# Board.net
KiCad netlist of a schematic drawn in EAGLE
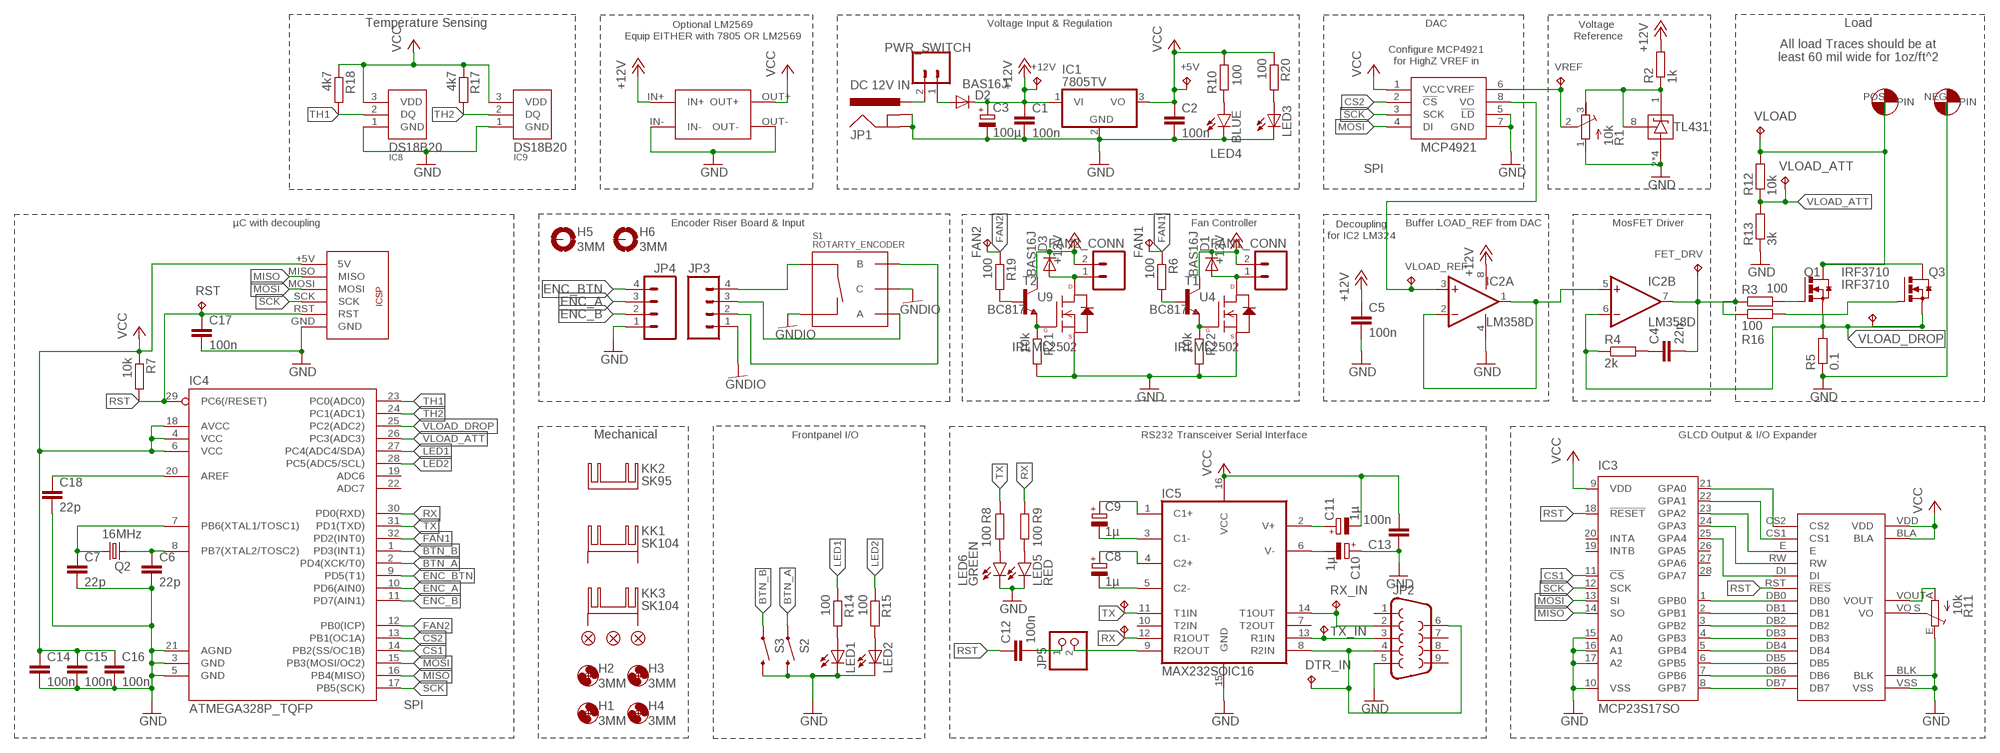
[diagram p0: schematic, sheet 1]

(export (version "E")
  (design (tool "Eeschema 10.0.6"))
  (components
    (comp (ref "+5V")
      (value "TPB1,27")
      (footprint "eagle-import:B1,27")
      (libsource (lib "eagle-import") (part "TPB1,27"))
    )
    (comp (ref "+12V")
      (value "TPB1,27")
      (footprint "eagle-import:B1,27")
      (libsource (lib "eagle-import") (part "TPB1,27"))
    )
    (comp (ref "C1")
      (value "100n")
      (footprint "eagle-import:C1206K")
      (libsource (lib "eagle-import") (part "C-EUC1206K"))
    )
    (comp (ref "C2")
      (value "100n")
      (footprint "eagle-import:C1206K")
      (libsource (lib "eagle-import") (part "C-EUC1206K"))
    )
    (comp (ref "C3")
      (value "100µ")
      (footprint "eagle-import:175TMP-0808")
      (libsource (lib "eagle-import") (part "CPOL-EU175TMP-0808"))
    )
    (comp (ref "C4")
      (value "22n")
      (footprint "eagle-import:C1206")
      (libsource (lib "eagle-import") (part "C-EUC1206"))
    )
    (comp (ref "C5")
      (value "100n")
      (footprint "eagle-import:C1206K")
      (libsource (lib "eagle-import") (part "C-EUC1206K"))
    )
    (comp (ref "C6")
      (value "22p")
      (footprint "eagle-import:C1206K")
      (libsource (lib "eagle-import") (part "C-EUC1206K"))
    )
    (comp (ref "C7")
      (value "22p")
      (footprint "eagle-import:C1206K")
      (libsource (lib "eagle-import") (part "C-EUC1206K"))
    )
    (comp (ref "C8")
      (value "1µ")
      (footprint "eagle-import:153CLV-0405")
      (libsource (lib "eagle-import") (part "CPOL-EU153CLV-0405"))
    )
    (comp (ref "C9")
      (value "1µ")
      (footprint "eagle-import:153CLV-0405")
      (libsource (lib "eagle-import") (part "CPOL-EU153CLV-0405"))
    )
    (comp (ref "C10")
      (value "1µ")
      (footprint "eagle-import:153CLV-0405")
      (libsource (lib "eagle-import") (part "CPOL-EU153CLV-0405"))
    )
    (comp (ref "C11")
      (value "1µ")
      (footprint "eagle-import:153CLV-0405")
      (libsource (lib "eagle-import") (part "CPOL-EU153CLV-0405"))
    )
    (comp (ref "C12")
      (value "100n")
      (footprint "eagle-import:C1206K")
      (libsource (lib "eagle-import") (part "C-EUC1206K"))
    )
    (comp (ref "C13")
      (value "100n")
      (footprint "eagle-import:C1206K")
      (libsource (lib "eagle-import") (part "C-EUC1206K"))
    )
    (comp (ref "C14")
      (value "100n")
      (footprint "eagle-import:C1206K")
      (libsource (lib "eagle-import") (part "C-EUC1206K"))
    )
    (comp (ref "C15")
      (value "100n")
      (footprint "eagle-import:C1206K")
      (libsource (lib "eagle-import") (part "C-EUC1206K"))
    )
    (comp (ref "C16")
      (value "100n")
      (footprint "eagle-import:C1206K")
      (libsource (lib "eagle-import") (part "C-EUC1206K"))
    )
    (comp (ref "C17")
      (value "100n")
      (footprint "eagle-import:C1206K")
      (libsource (lib "eagle-import") (part "C-EUC1206K"))
    )
    (comp (ref "C18")
      (value "22p")
      (footprint "eagle-import:C1206K")
      (libsource (lib "eagle-import") (part "C-EUC1206K"))
    )
    (comp (ref "D1")
      (value "BAS16J")
      (footprint "eagle-import:SOD323-W")
      (libsource (lib "eagle-import") (part "DIODE-SOD323-W"))
    )
    (comp (ref "D2")
      (value "BAS16J")
      (footprint "eagle-import:SOD323-W")
      (libsource (lib "eagle-import") (part "DIODE-SOD323-W"))
    )
    (comp (ref "D3")
      (value "BAS16J")
      (footprint "eagle-import:SOD323-W")
      (libsource (lib "eagle-import") (part "DIODE-SOD323-W"))
    )
    (comp (ref "DTR_IN")
      (value "TPB1,27")
      (footprint "eagle-import:B1,27")
      (libsource (lib "eagle-import") (part "TPB1,27"))
    )
    (comp (ref "FAN1")
      (value "TPB1,27")
      (footprint "eagle-import:B1,27")
      (libsource (lib "eagle-import") (part "TPB1,27"))
    )
    (comp (ref "FAN1_CONN")
      (value "M02POLAR")
      (footprint "eagle-import:MOLEX-1X2")
      (libsource (lib "eagle-import") (part "M02POLAR"))
    )
    (comp (ref "FAN2")
      (value "TPB1,27")
      (footprint "eagle-import:B1,27")
      (libsource (lib "eagle-import") (part "TPB1,27"))
    )
    (comp (ref "FAN2_CONN")
      (value "M02POLAR")
      (footprint "eagle-import:MOLEX-1X2")
      (libsource (lib "eagle-import") (part "M02POLAR"))
    )
    (comp (ref "FET_DRV")
      (value "TPB1,27")
      (footprint "eagle-import:B1,27")
      (libsource (lib "eagle-import") (part "TPB1,27"))
    )
    (comp (ref "FID1")
      (value "FIDUCIAL1X2")
      (footprint "eagle-import:FIDUCIAL-1X2")
      (libsource (lib "eagle-import") (part "FIDUCIAL1X2"))
    )
    (comp (ref "FID2")
      (value "FIDUCIAL1X2")
      (footprint "eagle-import:FIDUCIAL-1X2")
      (libsource (lib "eagle-import") (part "FIDUCIAL1X2"))
    )
    (comp (ref "FID3")
      (value "FIDUCIAL1X2")
      (footprint "eagle-import:FIDUCIAL-1X2")
      (libsource (lib "eagle-import") (part "FIDUCIAL1X2"))
    )
    (comp (ref "H1")
      (value "3MM")
      (footprint "eagle-import:3,0")
      (libsource (lib "eagle-import") (part "MOUNT-HOLE3.0"))
    )
    (comp (ref "H2")
      (value "3MM")
      (footprint "eagle-import:3,0")
      (libsource (lib "eagle-import") (part "MOUNT-HOLE3.0"))
    )
    (comp (ref "H3")
      (value "3MM")
      (footprint "eagle-import:3,0")
      (libsource (lib "eagle-import") (part "MOUNT-HOLE3.0"))
    )
    (comp (ref "H4")
      (value "3MM")
      (footprint "eagle-import:3,0")
      (libsource (lib "eagle-import") (part "MOUNT-HOLE3.0"))
    )
    (comp (ref "H5")
      (value "3MM")
      (footprint "eagle-import:3,0-PAD")
      (libsource (lib "eagle-import") (part "MOUNT-PAD-ROUND3.0"))
    )
    (comp (ref "H6")
      (value "3MM")
      (footprint "eagle-import:3,0-PAD")
      (libsource (lib "eagle-import") (part "MOUNT-PAD-ROUND3.0"))
    )
    (comp (ref "IC1")
      (value "7805TV")
      (footprint "eagle-import:TO220V")
      (libsource (lib "eagle-import") (part "78TV05"))
    )
    (comp (ref "IC2")
      (value "LM358D")
      (footprint "eagle-import:SO08")
      (libsource (lib "eagle-import") (part "LM358D"))
    )
    (comp (ref "IC3")
      (value "MCP23S17SO")
      (footprint "eagle-import:SO28W")
      (fields (field (name "MF") "MICROCHIP") (field (name "MPN") "MCP23S17-E/SO"))
      (libsource (lib "eagle-import") (part "MCP23S17SO"))
    )
    (comp (ref "IC4")
      (value "ATMEGA328P_TQFP")
      (footprint "eagle-import:TQFP32-08")
      (libsource (lib "eagle-import") (part "ATMEGA328P_TQFP"))
    )
    (comp (ref "IC5")
      (value "MAX232SOIC16")
      (footprint "eagle-import:SO016")
      (libsource (lib "eagle-import") (part "MAX232SOIC16"))
    )
    (comp (ref "IC6")
      (value "MCP4921")
      (footprint "eagle-import:SO-8")
      (libsource (lib "eagle-import") (part "MCP4921"))
    )
    (comp (ref "IC7")
      (value "TL431CD")
      (footprint "eagle-import:SO-8")
      (libsource (lib "eagle-import") (part "TL431CD"))
    )
    (comp (ref "IC8")
      (value "DS18B20")
      (footprint "eagle-import:TO-92")
      (libsource (lib "eagle-import") (part "DS18B20"))
    )
    (comp (ref "IC9")
      (value "DS18B20")
      (footprint "eagle-import:TO-92")
      (libsource (lib "eagle-import") (part "DS18B20"))
    )
    (comp (ref "JP1")
      (value "DC 12V IN")
      (footprint "eagle-import:POWER_JACK_PTH")
      (libsource (lib "eagle-import") (part "POWER_JACKPTH"))
    )
    (comp (ref "JP2")
      (value "DB9FEMALE")
      (footprint "eagle-import:DB9")
      (libsource (lib "eagle-import") (part "DB9FEMALE"))
    )
    (comp (ref "JP3")
      (value "M04POLAR")
      (footprint "eagle-import:MOLEX-1X4")
      (libsource (lib "eagle-import") (part "M04POLAR"))
    )
    (comp (ref "JP4")
      (value "M04POLAR")
      (footprint "eagle-import:MOLEX-1X4")
      (libsource (lib "eagle-import") (part "M04POLAR"))
    )
    (comp (ref "JP5")
      (value "PINHD-1X2")
      (footprint "eagle-import:1X02")
      (libsource (lib "eagle-import") (part "PINHD-1X2"))
    )
    (comp (ref "KK1")
      (value "SK104")
      (footprint "eagle-import:SK104-PAD")
      (libsource (lib "eagle-import") (part "SK104-PAD"))
    )
    (comp (ref "KK2")
      (value "SK95")
      (footprint "eagle-import:SK95-2M3")
      (libsource (lib "eagle-import") (part "SK95-2M3"))
    )
    (comp (ref "KK3")
      (value "SK104")
      (footprint "eagle-import:SK104-PAD")
      (libsource (lib "eagle-import") (part "SK104-PAD"))
    )
    (comp (ref "LED1")
      (value "LEDB155")
      (footprint "eagle-import:Q62902-B155")
      (libsource (lib "eagle-import") (part "LEDB155"))
    )
    (comp (ref "LED2")
      (value "LEDB155")
      (footprint "eagle-import:Q62902-B155")
      (libsource (lib "eagle-import") (part "LEDB155"))
    )
    (comp (ref "LED3")
      (value "LEDB155")
      (footprint "eagle-import:Q62902-B155")
      (libsource (lib "eagle-import") (part "LEDB155"))
    )
    (comp (ref "LED4")
      (value "BLUE")
      (footprint "eagle-import:LED-0603")
      (libsource (lib "eagle-import") (part "LED0603"))
    )
    (comp (ref "LED5")
      (value "RED")
      (footprint "eagle-import:LED-0603")
      (libsource (lib "eagle-import") (part "LED0603"))
    )
    (comp (ref "LED6")
      (value "GREEN")
      (footprint "eagle-import:LED-0603")
      (libsource (lib "eagle-import") (part "LED0603"))
    )
    (comp (ref "PWR_SWITCH")
      (value "M02POLAR")
      (footprint "eagle-import:MOLEX-1X2")
      (libsource (lib "eagle-import") (part "M02POLAR"))
    )
    (comp (ref "Q1")
      (value "IRF3710")
      (footprint "eagle-import:TO-220-V")
      (libsource (lib "eagle-import") (part "IRFZ44N"))
    )
    (comp (ref "Q2")
      (value "16MHz")
      (footprint "eagle-import:HC49UP")
      (libsource (lib "eagle-import") (part "CRYSTALHC49UP"))
    )
    (comp (ref "Q3")
      (value "IRF3710")
      (footprint "eagle-import:TO-220-V")
      (libsource (lib "eagle-import") (part "IRFZ44N"))
    )
    (comp (ref "R1")
      (value "10k")
      (footprint "eagle-import:RTRIM3296Y")
      (libsource (lib "eagle-import") (part "R-TRIMM3296Y"))
    )
    (comp (ref "R2")
      (value "1k")
      (footprint "eagle-import:M1206")
      (libsource (lib "eagle-import") (part "R-EU_M1206"))
    )
    (comp (ref "R3")
      (value "100")
      (footprint "eagle-import:R1206")
      (libsource (lib "eagle-import") (part "R-EU_R1206"))
    )
    (comp (ref "R4")
      (value "2k")
      (footprint "eagle-import:R1206")
      (libsource (lib "eagle-import") (part "R-EU_R1206"))
    )
    (comp (ref "R5")
      (value "0.1")
      (footprint "eagle-import:VTA52")
      (libsource (lib "eagle-import") (part "R-EU_VTA52"))
    )
    (comp (ref "R6")
      (value "100")
      (footprint "eagle-import:R1206")
      (libsource (lib "eagle-import") (part "R-EU_R1206"))
    )
    (comp (ref "R7")
      (value "10k")
      (footprint "eagle-import:R1206")
      (libsource (lib "eagle-import") (part "R-EU_R1206"))
    )
    (comp (ref "R8")
      (value "100")
      (footprint "eagle-import:R1206")
      (libsource (lib "eagle-import") (part "R-EU_R1206"))
    )
    (comp (ref "R9")
      (value "100")
      (footprint "eagle-import:R1206")
      (libsource (lib "eagle-import") (part "R-EU_R1206"))
    )
    (comp (ref "R10")
      (value "100")
      (footprint "eagle-import:R1206")
      (libsource (lib "eagle-import") (part "R-EU_R1206"))
    )
    (comp (ref "R11")
      (value "10k")
      (footprint "eagle-import:RS3")
      (libsource (lib "eagle-import") (part "TRIM_EU-RS3"))
    )
    (comp (ref "R12")
      (value "10k")
      (footprint "eagle-import:R1206")
      (libsource (lib "eagle-import") (part "R-EU_R1206"))
    )
    (comp (ref "R13")
      (value "3k")
      (footprint "eagle-import:R1206")
      (libsource (lib "eagle-import") (part "R-EU_R1206"))
    )
    (comp (ref "R14")
      (value "100")
      (footprint "eagle-import:R1206")
      (libsource (lib "eagle-import") (part "R-EU_R1206"))
    )
    (comp (ref "R15")
      (value "100")
      (footprint "eagle-import:R1206")
      (libsource (lib "eagle-import") (part "R-EU_R1206"))
    )
    (comp (ref "R16")
      (value "100")
      (footprint "eagle-import:R1206")
      (libsource (lib "eagle-import") (part "R-EU_R1206"))
    )
    (comp (ref "R17")
      (value "4k7")
      (footprint "eagle-import:M1206")
      (libsource (lib "eagle-import") (part "R-EU_M1206"))
    )
    (comp (ref "R18")
      (value "4k7")
      (footprint "eagle-import:M1206")
      (libsource (lib "eagle-import") (part "R-EU_M1206"))
    )
    (comp (ref "R19")
      (value "100")
      (footprint "eagle-import:R1206")
      (libsource (lib "eagle-import") (part "R-EU_R1206"))
    )
    (comp (ref "R20")
      (value "100")
      (footprint "eagle-import:R1206")
      (libsource (lib "eagle-import") (part "R-EU_R1206"))
    )
    (comp (ref "R21")
      (value "10k")
      (footprint "eagle-import:R1206")
      (libsource (lib "eagle-import") (part "R-EU_R1206"))
    )
    (comp (ref "R22")
      (value "10k")
      (footprint "eagle-import:R1206")
      (libsource (lib "eagle-import") (part "R-EU_R1206"))
    )
    (comp (ref "RST")
      (value "TPB1,27")
      (footprint "eagle-import:B1,27")
      (libsource (lib "eagle-import") (part "TPB1,27"))
    )
    (comp (ref "RX")
      (value "TPB1,27")
      (footprint "eagle-import:B1,27")
      (libsource (lib "eagle-import") (part "TPB1,27"))
    )
    (comp (ref "RX_IN")
      (value "TPB1,27")
      (footprint "eagle-import:B1,27")
      (libsource (lib "eagle-import") (part "TPB1,27"))
    )
    (comp (ref "S1")
      (value "ROTARTY_ENCODER")
      (footprint "eagle-import:ROTARY_ENC_PLAIN")
      (libsource (lib "eagle-import") (part "ROTARTY_ENCODER"))
    )
    (comp (ref "S2")
      (value "SWITCH-MOMENTARY-2SIDE_EZ")
      (footprint "eagle-import:TACTILE-PTH-SIDEEZ")
      (libsource (lib "eagle-import") (part "SWITCH-MOMENTARY-2SIDE_EZ"))
    )
    (comp (ref "S3")
      (value "SWITCH-MOMENTARY-2SIDE_EZ")
      (footprint "eagle-import:TACTILE-PTH-SIDEEZ")
      (libsource (lib "eagle-import") (part "SWITCH-MOMENTARY-2SIDE_EZ"))
    )
    (comp (ref "T1")
      (value "BC817")
      (footprint "eagle-import:SOT23-BEC")
      (libsource (lib "eagle-import") (part "-NPN-SOT23-BECBC817"))
    )
    (comp (ref "T2")
      (value "BC817")
      (footprint "eagle-import:SOT23-BEC")
      (libsource (lib "eagle-import") (part "-NPN-SOT23-BECBC817"))
    )
    (comp (ref "TX")
      (value "TPB1,27")
      (footprint "eagle-import:B1,27")
      (libsource (lib "eagle-import") (part "TPB1,27"))
    )
    (comp (ref "TX_IN")
      (value "TPB1,27")
      (footprint "eagle-import:B1,27")
      (libsource (lib "eagle-import") (part "TPB1,27"))
    )
    (comp (ref "U$3")
      (value "CON-2-HIGAMP")
      (footprint "eagle-import:CON-HIGHAMP-0.3_")
      (libsource (lib "eagle-import") (part "CON-2-HIGAMP"))
    )
    (comp (ref "U$5")
      (value "ICSPTHROUGHHOLE")
      (footprint "eagle-import:ICSP-THROUGHHOLE")
      (libsource (lib "eagle-import") (part "ICSPTHROUGHHOLE"))
    )
    (comp (ref "U$6")
      (value "KS0108-GLCDS6B0108")
      (footprint "eagle-import:KS0108-S6B0108-GLCD")
      (libsource (lib "eagle-import") (part "KS0108-GLCDS6B0108"))
    )
    (comp (ref "U$10")
      (value "LM2569NO_OUTLINE")
      (footprint "eagle-import:LM2596_NO_OUTLINE")
      (libsource (lib "eagle-import") (part "LM2569NO_OUTLINE"))
    )
    (comp (ref "U4")
      (value "IRLML2502")
      (footprint "eagle-import:SOT23-3")
      (libsource (lib "eagle-import") (part "N-CHANNEL-MOSFET-BSS138"))
    )
    (comp (ref "U9")
      (value "IRLML2502")
      (footprint "eagle-import:SOT23-3")
      (libsource (lib "eagle-import") (part "N-CHANNEL-MOSFET-BSS138"))
    )
    (comp (ref "VLOAD")
      (value "TPB1,27")
      (footprint "eagle-import:B1,27")
      (libsource (lib "eagle-import") (part "TPB1,27"))
    )
    (comp (ref "VLOAD_ATT")
      (value "TPB1,27")
      (footprint "eagle-import:B1,27")
      (libsource (lib "eagle-import") (part "TPB1,27"))
    )
    (comp (ref "VLOAD_DROP")
      (value "TPB1,27")
      (footprint "eagle-import:B1,27")
      (libsource (lib "eagle-import") (part "TPB1,27"))
    )
    (comp (ref "VLOAD_REF")
      (value "TPB1,27")
      (footprint "eagle-import:B1,27")
      (libsource (lib "eagle-import") (part "TPB1,27"))
    )
    (comp (ref "VREF")
      (value "TPB1,27")
      (footprint "eagle-import:B1,27")
      (libsource (lib "eagle-import") (part "TPB1,27"))
    )
  )
  (nets
    (net (code "1") (name "+12V") (class "Default")
      (node (ref "+12V") (pin "TP") (pinfunction "TP_TP") (pintype "input"))
      (node (ref "C1") (pin "1") (pinfunction "1_1") (pintype "passive"))
      (node (ref "C3") (pin "+") (pinfunction "+_+") (pintype "passive"))
      (node (ref "C5") (pin "1") (pinfunction "1_1") (pintype "passive"))
      (node (ref "D1") (pin "C") (pinfunction "C_C") (pintype "passive"))
      (node (ref "D2") (pin "C") (pinfunction "C_C") (pintype "passive"))
      (node (ref "D3") (pin "C") (pinfunction "C_C") (pintype "passive"))
      (node (ref "FAN1_CONN") (pin "2") (pinfunction "2_2") (pintype "passive"))
      (node (ref "FAN2_CONN") (pin "2") (pinfunction "2_2") (pintype "passive"))
      (node (ref "IC1") (pin "1") (pinfunction "VI_1") (pintype "input"))
      (node (ref "IC2") (pin "8") (pinfunction "V+_8") (pintype "power_in"))
      (node (ref "R2") (pin "2") (pinfunction "2_2") (pintype "passive"))
      (node (ref "T1") (pin "C") (pinfunction "C_C") (pintype "passive"))
      (node (ref "T2") (pin "C") (pinfunction "C_C") (pintype "passive"))
      (node (ref "U$10") (pin "IN+") (pinfunction "IN+_IN+") (pintype "bidirectional"))
    )
    (net (code "2") (name "BTN_A") (class "Default")
      (node (ref "IC4") (pin "2") (pinfunction "PD4(XCK/T0)_2") (pintype "bidirectional"))
      (node (ref "S2") (pin "1") (pinfunction "1_1") (pintype "passive"))
    )
    (net (code "3") (name "BTN_B") (class "Default")
      (node (ref "IC4") (pin "1") (pinfunction "PD3(INT1)_1") (pintype "bidirectional"))
      (node (ref "S3") (pin "1") (pinfunction "1_1") (pintype "passive"))
    )
    (net (code "4") (name "CS1") (class "Default")
      (node (ref "IC3") (pin "11") (pinfunction "~{CS}_11") (pintype "input"))
      (node (ref "IC4") (pin "14") (pinfunction "PB2(SS/OC1B)_14") (pintype "bidirectional"))
    )
    (net (code "5") (name "CS2") (class "Default")
      (node (ref "IC4") (pin "13") (pinfunction "PB1(OC1A)_13") (pintype "bidirectional"))
      (node (ref "IC6") (pin "2") (pinfunction "~{CS}_2") (pintype "bidirectional"))
    )
    (net (code "6") (name "ENC_A") (class "Default")
      (node (ref "IC4") (pin "10") (pinfunction "PD6(AIN0)_10") (pintype "bidirectional"))
      (node (ref "JP4") (pin "3") (pinfunction "3_3") (pintype "passive"))
    )
    (net (code "7") (name "ENC_B") (class "Default")
      (node (ref "IC4") (pin "11") (pinfunction "PD7(AIN1)_11") (pintype "bidirectional"))
      (node (ref "JP4") (pin "2") (pinfunction "2_2") (pintype "passive"))
    )
    (net (code "8") (name "ENC_BTN") (class "Default")
      (node (ref "IC4") (pin "9") (pinfunction "PD5(T1)_9") (pintype "bidirectional"))
      (node (ref "JP4") (pin "4") (pinfunction "4_4") (pintype "passive"))
    )
    (net (code "9") (name "FAN1") (class "Default")
      (node (ref "FAN1") (pin "TP") (pinfunction "TP_TP") (pintype "input"))
      (node (ref "IC4") (pin "32") (pinfunction "PD2(INT0)_32") (pintype "bidirectional"))
      (node (ref "R6") (pin "1") (pinfunction "1_1") (pintype "passive"))
    )
    (net (code "10") (name "FAN2") (class "Default")
      (node (ref "FAN2") (pin "TP") (pinfunction "TP_TP") (pintype "input"))
      (node (ref "IC4") (pin "12") (pinfunction "PB0(ICP)_12") (pintype "bidirectional"))
      (node (ref "R19") (pin "1") (pinfunction "1_1") (pintype "passive"))
    )
    (net (code "11") (name "GND") (class "Default")
      (node (ref "C1") (pin "2") (pinfunction "2_2") (pintype "passive"))
      (node (ref "C10") (pin "+") (pinfunction "+_+") (pintype "passive"))
      (node (ref "C13") (pin "1") (pinfunction "1_1") (pintype "passive"))
      (node (ref "C14") (pin "2") (pinfunction "2_2") (pintype "passive"))
      (node (ref "C15") (pin "2") (pinfunction "2_2") (pintype "passive"))
      (node (ref "C16") (pin "2") (pinfunction "2_2") (pintype "passive"))
      (node (ref "C17") (pin "2") (pinfunction "2_2") (pintype "passive"))
      (node (ref "C18") (pin "2") (pinfunction "2_2") (pintype "passive"))
      (node (ref "C2") (pin "2") (pinfunction "2_2") (pintype "passive"))
      (node (ref "C3") (pin "-") (pinfunction "-_-") (pintype "passive"))
      (node (ref "C5") (pin "2") (pinfunction "2_2") (pintype "passive"))
      (node (ref "C6") (pin "2") (pinfunction "2_2") (pintype "passive"))
      (node (ref "C7") (pin "2") (pinfunction "2_2") (pintype "passive"))
      (node (ref "IC1") (pin "2") (pinfunction "GND_2") (pintype "passive"))
      (node (ref "IC2") (pin "4") (pinfunction "V-_4") (pintype "power_in"))
      (node (ref "IC3") (pin "10") (pinfunction "VSS_10") (pintype "power_in"))
      (node (ref "IC3") (pin "15") (pinfunction "A0_15") (pintype "input"))
      (node (ref "IC3") (pin "16") (pinfunction "A1_16") (pintype "input"))
      (node (ref "IC3") (pin "17") (pinfunction "A2_17") (pintype "input"))
      (node (ref "IC4") (pin "21") (pinfunction "AGND_21") (pintype "bidirectional"))
      (node (ref "IC4") (pin "3") (pinfunction "GND_3") (pintype "bidirectional"))
      (node (ref "IC4") (pin "5") (pinfunction "GND_5") (pintype "bidirectional"))
      (node (ref "IC5") (pin "15") (pinfunction "GND_15") (pintype "bidirectional"))
      (node (ref "IC6") (pin "5") (pinfunction "~{LD}_5") (pintype "input"))
      (node (ref "IC6") (pin "7") (pinfunction "GND_7") (pintype "power_in"))
      (node (ref "IC7") (pin "2") (pinfunction "ANODE_2") (pintype "passive"))
      (node (ref "IC7") (pin "3") (pinfunction "ANODE_3") (pintype "passive"))
      (node (ref "IC7") (pin "6") (pinfunction "ANODE_6") (pintype "passive"))
      (node (ref "IC7") (pin "7") (pinfunction "ANODE_7") (pintype "passive"))
      (node (ref "IC8") (pin "1") (pinfunction "GND_1") (pintype "power_in"))
      (node (ref "IC9") (pin "1") (pinfunction "GND_1") (pintype "power_in"))
      (node (ref "JP1") (pin "GND") (pinfunction "GND_GND") (pintype "bidirectional"))
      (node (ref "JP1") (pin "GNDBREAK") (pinfunction "GNDBREAK_GNDBREAK") (pintype "bidirectional"))
      (node (ref "JP2") (pin "5") (pinfunction "5_5") (pintype "passive"))
      (node (ref "JP4") (pin "1") (pinfunction "1_1") (pintype "passive"))
      (node (ref "LED1") (pin "K") (pinfunction "C_K") (pintype "passive"))
      (node (ref "LED2") (pin "K") (pinfunction "C_K") (pintype "passive"))
      (node (ref "LED3") (pin "K") (pinfunction "C_K") (pintype "passive"))
      (node (ref "LED4") (pin "C") (pinfunction "C_C") (pintype "passive"))
      (node (ref "LED5") (pin "C") (pinfunction "C_C") (pintype "passive"))
      (node (ref "LED6") (pin "C") (pinfunction "C_C") (pintype "passive"))
      (node (ref "R1") (pin "1") (pinfunction "A_1") (pintype "passive"))
      (node (ref "R11") (pin "E") (pinfunction "E_E") (pintype "passive"))
      (node (ref "R13") (pin "1") (pinfunction "1_1") (pintype "passive"))
      (node (ref "R21") (pin "2") (pinfunction "2_2") (pintype "passive"))
      (node (ref "R22") (pin "2") (pinfunction "2_2") (pintype "passive"))
      (node (ref "R5") (pin "1") (pinfunction "1_1") (pintype "passive"))
      (node (ref "S2") (pin "2") (pinfunction "2_2") (pintype "passive"))
      (node (ref "S3") (pin "2") (pinfunction "2_2") (pintype "passive"))
      (node (ref "U$10") (pin "IN-") (pinfunction "IN-_IN-") (pintype "bidirectional"))
      (node (ref "U$10") (pin "OUT-") (pinfunction "OUT-_OUT-") (pintype "bidirectional"))
      (node (ref "U$3") (pin "NEG") (pinfunction "PIN_NEG") (pintype "bidirectional"))
      (node (ref "U$5") (pin "GND") (pinfunction "GND_GND") (pintype "bidirectional"))
      (node (ref "U$6") (pin "BLK") (pinfunction "BLK_BLK") (pintype "bidirectional"))
      (node (ref "U$6") (pin "VSS") (pinfunction "VSS_VSS") (pintype "bidirectional"))
      (node (ref "U4") (pin "2") (pinfunction "S_2") (pintype "passive"))
      (node (ref "U9") (pin "2") (pinfunction "S_2") (pintype "passive"))
    )
    (net (code "12") (name "GNDIO") (class "Default")
      (node (ref "JP3") (pin "1") (pinfunction "1_1") (pintype "passive"))
      (node (ref "S1") (pin "C") (pinfunction "C_C") (pintype "bidirectional"))
      (node (ref "S1") (pin "SW-") (pinfunction "SW-_SW-") (pintype "bidirectional"))
    )
    (net (code "13") (name "LED1") (class "Default")
      (node (ref "IC4") (pin "27") (pinfunction "PC4(ADC4/SDA)_27") (pintype "bidirectional"))
      (node (ref "R14") (pin "1") (pinfunction "1_1") (pintype "passive"))
    )
    (net (code "14") (name "LED2") (class "Default")
      (node (ref "IC4") (pin "28") (pinfunction "PC5(ADC5/SCL)_28") (pintype "bidirectional"))
      (node (ref "R15") (pin "1") (pinfunction "1_1") (pintype "passive"))
    )
    (net (code "15") (name "MISO") (class "Default")
      (node (ref "IC3") (pin "14") (pinfunction "SO_14") (pintype "output"))
      (node (ref "IC4") (pin "16") (pinfunction "PB4(MISO)_16") (pintype "bidirectional"))
      (node (ref "U$5") (pin "MISO") (pinfunction "MISO_MISO") (pintype "bidirectional"))
    )
    (net (code "16") (name "MOSI") (class "Default")
      (node (ref "IC3") (pin "13") (pinfunction "SI_13") (pintype "input"))
      (node (ref "IC4") (pin "15") (pinfunction "PB3(MOSI/OC2)_15") (pintype "bidirectional"))
      (node (ref "IC6") (pin "4") (pinfunction "DI_4") (pintype "bidirectional"))
      (node (ref "U$5") (pin "MOSI") (pinfunction "MOSI_MOSI") (pintype "bidirectional"))
    )
    (net (code "17") (name "Net-(C4-Pad1)") (class "Default")
      (node (ref "C4") (pin "1") (pinfunction "1_1") (pintype "passive"))
      (node (ref "R4") (pin "2") (pinfunction "2_2") (pintype "passive"))
    )
    (net (code "18") (name "Net-(C12-Pad2)") (class "Default")
      (node (ref "C12") (pin "2") (pinfunction "2_2") (pintype "passive"))
      (node (ref "JP5") (pin "1") (pinfunction "1_1") (pintype "passive"))
    )
    (net (code "19") (name "Net-(D2-PadA)") (class "Default")
      (node (ref "D2") (pin "A") (pinfunction "A_A") (pintype "passive"))
      (node (ref "PWR_SWITCH") (pin "1") (pinfunction "1_1") (pintype "passive"))
    )
    (net (code "20") (name "Net-(IC2A-+IN)") (class "Default")
      (node (ref "IC2") (pin "3") (pinfunction "+IN_3") (pintype "input"))
      (node (ref "IC6") (pin "8") (pinfunction "VO_8") (pintype "output"))
      (node (ref "VLOAD_REF") (pin "TP") (pinfunction "TP_TP") (pintype "input"))
    )
    (net (code "21") (name "Net-(IC2A--IN)") (class "Default")
      (node (ref "IC2") (pin "1") (pinfunction "OUT_1") (pintype "output"))
      (node (ref "IC2") (pin "2") (pinfunction "-IN_2") (pintype "input"))
      (node (ref "IC2") (pin "5") (pinfunction "+IN_5") (pintype "input"))
    )
    (net (code "22") (name "Net-(IC2B-OUT)") (class "Default")
      (node (ref "C4") (pin "2") (pinfunction "2_2") (pintype "passive"))
      (node (ref "FET_DRV") (pin "TP") (pinfunction "TP_TP") (pintype "input"))
      (node (ref "IC2") (pin "7") (pinfunction "OUT_7") (pintype "output"))
      (node (ref "R16") (pin "1") (pinfunction "1_1") (pintype "passive"))
      (node (ref "R3") (pin "1") (pinfunction "1_1") (pintype "passive"))
    )
    (net (code "23") (name "Net-(IC3-GPA0)") (class "Default")
      (node (ref "IC3") (pin "21") (pinfunction "GPA0_21") (pintype "bidirectional"))
      (node (ref "U$6") (pin "CS2") (pinfunction "CS2_CS2") (pintype "bidirectional"))
    )
    (net (code "24") (name "Net-(IC3-GPA1)") (class "Default")
      (node (ref "IC3") (pin "22") (pinfunction "GPA1_22") (pintype "bidirectional"))
      (node (ref "U$6") (pin "CS1") (pinfunction "CS1_CS1") (pintype "bidirectional"))
    )
    (net (code "25") (name "Net-(IC3-GPA2)") (class "Default")
      (node (ref "IC3") (pin "23") (pinfunction "GPA2_23") (pintype "bidirectional"))
      (node (ref "U$6") (pin "E") (pinfunction "E_E") (pintype "bidirectional"))
    )
    (net (code "26") (name "Net-(IC3-GPA3)") (class "Default")
      (node (ref "IC3") (pin "24") (pinfunction "GPA3_24") (pintype "bidirectional"))
      (node (ref "U$6") (pin "RW") (pinfunction "RW_RW") (pintype "bidirectional"))
    )
    (net (code "27") (name "Net-(IC3-GPA4)") (class "Default")
      (node (ref "IC3") (pin "25") (pinfunction "GPA4_25") (pintype "bidirectional"))
      (node (ref "U$6") (pin "DI") (pinfunction "DI_DI") (pintype "bidirectional"))
    )
    (net (code "28") (name "Net-(IC3-GPB0)") (class "Default")
      (node (ref "IC3") (pin "1") (pinfunction "GPB0_1") (pintype "bidirectional"))
      (node (ref "U$6") (pin "DB0") (pinfunction "DB0_DB0") (pintype "bidirectional"))
    )
    (net (code "29") (name "Net-(IC3-GPB1)") (class "Default")
      (node (ref "IC3") (pin "2") (pinfunction "GPB1_2") (pintype "bidirectional"))
      (node (ref "U$6") (pin "DB1") (pinfunction "DB1_DB1") (pintype "bidirectional"))
    )
    (net (code "30") (name "Net-(IC3-GPB2)") (class "Default")
      (node (ref "IC3") (pin "3") (pinfunction "GPB2_3") (pintype "bidirectional"))
      (node (ref "U$6") (pin "DB2") (pinfunction "DB2_DB2") (pintype "bidirectional"))
    )
    (net (code "31") (name "Net-(IC3-GPB3)") (class "Default")
      (node (ref "IC3") (pin "4") (pinfunction "GPB3_4") (pintype "bidirectional"))
      (node (ref "U$6") (pin "DB3") (pinfunction "DB3_DB3") (pintype "bidirectional"))
    )
    (net (code "32") (name "Net-(IC3-GPB4)") (class "Default")
      (node (ref "IC3") (pin "5") (pinfunction "GPB4_5") (pintype "bidirectional"))
      (node (ref "U$6") (pin "DB4") (pinfunction "DB4_DB4") (pintype "bidirectional"))
    )
    (net (code "33") (name "Net-(IC3-GPB5)") (class "Default")
      (node (ref "IC3") (pin "6") (pinfunction "GPB5_6") (pintype "bidirectional"))
      (node (ref "U$6") (pin "DB5") (pinfunction "DB5_DB5") (pintype "bidirectional"))
    )
    (net (code "34") (name "Net-(IC3-GPB6)") (class "Default")
      (node (ref "IC3") (pin "7") (pinfunction "GPB6_7") (pintype "bidirectional"))
      (node (ref "U$6") (pin "DB6") (pinfunction "DB6_DB6") (pintype "bidirectional"))
    )
    (net (code "35") (name "Net-(IC3-GPB7)") (class "Default")
      (node (ref "IC3") (pin "8") (pinfunction "GPB7_8") (pintype "bidirectional"))
      (node (ref "U$6") (pin "DB7") (pinfunction "DB7_DB7") (pintype "bidirectional"))
    )
    (net (code "36") (name "Net-(IC4-AREF)") (class "Default")
      (node (ref "C18") (pin "1") (pinfunction "1_1") (pintype "passive"))
      (node (ref "IC4") (pin "20") (pinfunction "AREF_20") (pintype "bidirectional"))
    )
    (net (code "37") (name "Net-(IC4-PB6(XTAL1{slash}TOSC1))") (class "Default")
      (node (ref "C7") (pin "1") (pinfunction "1_1") (pintype "passive"))
      (node (ref "IC4") (pin "7") (pinfunction "PB6(XTAL1/TOSC1)_7") (pintype "bidirectional"))
      (node (ref "Q2") (pin "1") (pinfunction "1_1") (pintype "passive"))
    )
    (net (code "38") (name "Net-(IC4-PB7(XTAL2{slash}TOSC2))") (class "Default")
      (node (ref "C6") (pin "1") (pinfunction "1_1") (pintype "passive"))
      (node (ref "IC4") (pin "8") (pinfunction "PB7(XTAL2/TOSC2)_8") (pintype "bidirectional"))
      (node (ref "Q2") (pin "2") (pinfunction "2_2") (pintype "passive"))
    )
    (net (code "39") (name "Net-(IC5-C1+)") (class "Default")
      (node (ref "C9") (pin "+") (pinfunction "+_+") (pintype "passive"))
      (node (ref "IC5") (pin "1") (pinfunction "C1+_1") (pintype "bidirectional"))
    )
    (net (code "40") (name "Net-(IC5-C1-)") (class "Default")
      (node (ref "C9") (pin "-") (pinfunction "-_-") (pintype "passive"))
      (node (ref "IC5") (pin "3") (pinfunction "C1-_3") (pintype "bidirectional"))
    )
    (net (code "41") (name "Net-(IC5-C2+)") (class "Default")
      (node (ref "C8") (pin "+") (pinfunction "+_+") (pintype "passive"))
      (node (ref "IC5") (pin "4") (pinfunction "C2+_4") (pintype "bidirectional"))
    )
    (net (code "42") (name "Net-(IC5-C2-)") (class "Default")
      (node (ref "C8") (pin "-") (pinfunction "-_-") (pintype "passive"))
      (node (ref "IC5") (pin "5") (pinfunction "C2-_5") (pintype "bidirectional"))
    )
    (net (code "43") (name "Net-(IC5-R1IN)") (class "Default")
      (node (ref "IC5") (pin "13") (pinfunction "R1IN_13") (pintype "input"))
      (node (ref "JP2") (pin "3") (pinfunction "3_3") (pintype "passive"))
      (node (ref "TX_IN") (pin "TP") (pinfunction "TP_TP") (pintype "input"))
    )
    (net (code "44") (name "Net-(IC5-R2IN)") (class "Default")
      (node (ref "DTR_IN") (pin "TP") (pinfunction "TP_TP") (pintype "input"))
      (node (ref "IC5") (pin "8") (pinfunction "R2IN_8") (pintype "input"))
      (node (ref "JP2") (pin "4") (pinfunction "4_4") (pintype "passive"))
      (node (ref "JP2") (pin "6") (pinfunction "6_6") (pintype "passive"))
    )
    (net (code "45") (name "Net-(IC5-R2OUT)") (class "Default")
      (node (ref "IC5") (pin "9") (pinfunction "R2OUT_9") (pintype "output"))
      (node (ref "JP5") (pin "2") (pinfunction "2_2") (pintype "passive"))
    )
    (net (code "46") (name "Net-(IC5-T1OUT)") (class "Default")
      (node (ref "IC5") (pin "14") (pinfunction "T1OUT_14") (pintype "output"))
      (node (ref "JP2") (pin "2") (pinfunction "2_2") (pintype "passive"))
      (node (ref "RX_IN") (pin "TP") (pinfunction "TP_TP") (pintype "input"))
    )
    (net (code "47") (name "Net-(IC5-V+)") (class "Default")
      (node (ref "C11") (pin "+") (pinfunction "+_+") (pintype "passive"))
      (node (ref "IC5") (pin "2") (pinfunction "V+_2") (pintype "bidirectional"))
    )
    (net (code "48") (name "Net-(IC5-V-)") (class "Default")
      (node (ref "C10") (pin "-") (pinfunction "-_-") (pintype "passive"))
      (node (ref "IC5") (pin "6") (pinfunction "V-_6") (pintype "bidirectional"))
    )
    (net (code "49") (name "Net-(IC6-VREF)") (class "Default")
      (node (ref "IC6") (pin "6") (pinfunction "VREF_6") (pintype "input"))
      (node (ref "R1") (pin "2") (pinfunction "S_2") (pintype "passive"))
      (node (ref "VREF") (pin "TP") (pinfunction "TP_TP") (pintype "input"))
    )
    (net (code "50") (name "Net-(IC7-CATHODE)") (class "Default")
      (node (ref "IC7") (pin "1") (pinfunction "CATHODE_1") (pintype "passive"))
      (node (ref "IC7") (pin "8") (pinfunction "REF_8") (pintype "passive"))
      (node (ref "R1") (pin "3") (pinfunction "E_3") (pintype "passive"))
      (node (ref "R2") (pin "1") (pinfunction "1_1") (pintype "passive"))
    )
    (net (code "51") (name "Net-(JP1-PadPWR)") (class "Default")
      (node (ref "JP1") (pin "PWR") (pinfunction "PWR_PWR") (pintype "bidirectional"))
      (node (ref "PWR_SWITCH") (pin "2") (pinfunction "2_2") (pintype "passive"))
    )
    (net (code "52") (name "Net-(JP3-Pad2)") (class "Default")
      (node (ref "JP3") (pin "2") (pinfunction "2_2") (pintype "passive"))
      (node (ref "S1") (pin "B") (pinfunction "B_B") (pintype "bidirectional"))
    )
    (net (code "53") (name "Net-(JP3-Pad3)") (class "Default")
      (node (ref "JP3") (pin "3") (pinfunction "3_3") (pintype "passive"))
      (node (ref "S1") (pin "A") (pinfunction "A_A") (pintype "bidirectional"))
    )
    (net (code "54") (name "Net-(JP3-Pad4)") (class "Default")
      (node (ref "JP3") (pin "4") (pinfunction "4_4") (pintype "passive"))
      (node (ref "S1") (pin "SW+") (pinfunction "SW+_SW+") (pintype "bidirectional"))
    )
    (net (code "55") (name "Net-(LED1-PadA)") (class "Default")
      (node (ref "LED1") (pin "A") (pinfunction "A_A") (pintype "passive"))
      (node (ref "R14") (pin "2") (pinfunction "2_2") (pintype "passive"))
    )
    (net (code "56") (name "Net-(LED2-PadA)") (class "Default")
      (node (ref "LED2") (pin "A") (pinfunction "A_A") (pintype "passive"))
      (node (ref "R15") (pin "2") (pinfunction "2_2") (pintype "passive"))
    )
    (net (code "57") (name "Net-(LED3-PadA)") (class "Default")
      (node (ref "LED3") (pin "A") (pinfunction "A_A") (pintype "passive"))
      (node (ref "R20") (pin "2") (pinfunction "2_2") (pintype "passive"))
    )
    (net (code "58") (name "Net-(LED4-PadA)") (class "Default")
      (node (ref "LED4") (pin "A") (pinfunction "A_A") (pintype "passive"))
      (node (ref "R10") (pin "2") (pinfunction "2_2") (pintype "passive"))
    )
    (net (code "59") (name "Net-(LED5-PadA)") (class "Default")
      (node (ref "LED5") (pin "A") (pinfunction "A_A") (pintype "passive"))
      (node (ref "R9") (pin "2") (pinfunction "2_2") (pintype "passive"))
    )
    (net (code "60") (name "Net-(LED6-PadA)") (class "Default")
      (node (ref "LED6") (pin "A") (pinfunction "A_A") (pintype "passive"))
      (node (ref "R8") (pin "2") (pinfunction "2_2") (pintype "passive"))
    )
    (net (code "61") (name "Net-(Q1-D)") (class "Default")
      (node (ref "Q1") (pin "2") (pinfunction "D_2") (pintype "passive"))
      (node (ref "Q3") (pin "2") (pinfunction "D_2") (pintype "passive"))
      (node (ref "R12") (pin "2") (pinfunction "2_2") (pintype "passive"))
      (node (ref "U$3") (pin "POS") (pinfunction "PIN_POS") (pintype "bidirectional"))
      (node (ref "VLOAD") (pin "TP") (pinfunction "TP_TP") (pintype "input"))
    )
    (net (code "62") (name "Net-(Q1-G)") (class "Default")
      (node (ref "Q1") (pin "1") (pinfunction "G_1") (pintype "passive"))
      (node (ref "R3") (pin "2") (pinfunction "2_2") (pintype "passive"))
    )
    (net (code "63") (name "Net-(Q3-G)") (class "Default")
      (node (ref "Q3") (pin "1") (pinfunction "G_1") (pintype "passive"))
      (node (ref "R16") (pin "2") (pinfunction "2_2") (pintype "passive"))
    )
    (net (code "64") (name "Net-(R6-Pad2)") (class "Default")
      (node (ref "R6") (pin "2") (pinfunction "2_2") (pintype "passive"))
      (node (ref "T1") (pin "B") (pinfunction "B_B") (pintype "passive"))
    )
    (net (code "65") (name "Net-(R11-PadA)") (class "Default")
      (node (ref "R11") (pin "A") (pinfunction "A_A") (pintype "passive"))
      (node (ref "U$6") (pin "VOUT") (pinfunction "VOUT_VOUT") (pintype "bidirectional"))
    )
    (net (code "66") (name "Net-(R11-PadS)") (class "Default")
      (node (ref "R11") (pin "S") (pinfunction "S_S") (pintype "passive"))
      (node (ref "U$6") (pin "VO") (pinfunction "VO_VO") (pintype "bidirectional"))
    )
    (net (code "67") (name "Net-(R19-Pad2)") (class "Default")
      (node (ref "R19") (pin "2") (pinfunction "2_2") (pintype "passive"))
      (node (ref "T2") (pin "B") (pinfunction "B_B") (pintype "passive"))
    )
    (net (code "68") (name "Net-(U4-D)") (class "Default")
      (node (ref "D1") (pin "A") (pinfunction "A_A") (pintype "passive"))
      (node (ref "FAN1_CONN") (pin "1") (pinfunction "1_1") (pintype "passive"))
      (node (ref "U4") (pin "3") (pinfunction "D_3") (pintype "passive"))
    )
    (net (code "69") (name "Net-(U4-G)") (class "Default")
      (node (ref "R22") (pin "1") (pinfunction "1_1") (pintype "passive"))
      (node (ref "T1") (pin "E") (pinfunction "E_E") (pintype "passive"))
      (node (ref "U4") (pin "1") (pinfunction "G_1") (pintype "passive"))
    )
    (net (code "70") (name "Net-(U9-D)") (class "Default")
      (node (ref "D3") (pin "A") (pinfunction "A_A") (pintype "passive"))
      (node (ref "FAN2_CONN") (pin "1") (pinfunction "1_1") (pintype "passive"))
      (node (ref "U9") (pin "3") (pinfunction "D_3") (pintype "passive"))
    )
    (net (code "71") (name "Net-(U9-G)") (class "Default")
      (node (ref "R21") (pin "1") (pinfunction "1_1") (pintype "passive"))
      (node (ref "T2") (pin "E") (pinfunction "E_E") (pintype "passive"))
      (node (ref "U9") (pin "1") (pinfunction "G_1") (pintype "passive"))
    )
    (net (code "72") (name "RST") (class "Default")
      (node (ref "C12") (pin "1") (pinfunction "1_1") (pintype "passive"))
      (node (ref "C17") (pin "1") (pinfunction "1_1") (pintype "passive"))
      (node (ref "IC3") (pin "18") (pinfunction "~{RESET}_18") (pintype "input"))
      (node (ref "IC4") (pin "29") (pinfunction "PC6(/RESET)_29") (pintype "bidirectional"))
      (node (ref "R7") (pin "2") (pinfunction "2_2") (pintype "passive"))
      (node (ref "RST") (pin "TP") (pinfunction "TP_TP") (pintype "input"))
      (node (ref "U$5") (pin "RST") (pinfunction "RST_RST") (pintype "bidirectional"))
      (node (ref "U$6") (pin "RST") (pinfunction "~{RES}_RST") (pintype "bidirectional"))
    )
    (net (code "73") (name "RX") (class "Default")
      (node (ref "IC4") (pin "30") (pinfunction "PD0(RXD)_30") (pintype "bidirectional"))
      (node (ref "IC5") (pin "12") (pinfunction "R1OUT_12") (pintype "output"))
      (node (ref "R9") (pin "1") (pinfunction "1_1") (pintype "passive"))
      (node (ref "RX") (pin "TP") (pinfunction "TP_TP") (pintype "input"))
    )
    (net (code "74") (name "SCK") (class "Default")
      (node (ref "IC3") (pin "12") (pinfunction "SCK_12") (pintype "input"))
      (node (ref "IC4") (pin "17") (pinfunction "PB5(SCK)_17") (pintype "bidirectional"))
      (node (ref "IC6") (pin "3") (pinfunction "SCK_3") (pintype "bidirectional"))
      (node (ref "U$5") (pin "SCK") (pinfunction "SCK_SCK") (pintype "bidirectional"))
    )
    (net (code "75") (name "TH1") (class "Default")
      (node (ref "IC4") (pin "23") (pinfunction "PC0(ADC0)_23") (pintype "bidirectional"))
      (node (ref "IC8") (pin "2") (pinfunction "DQ_2") (pintype "bidirectional"))
      (node (ref "R18") (pin "2") (pinfunction "2_2") (pintype "passive"))
    )
    (net (code "76") (name "TH2") (class "Default")
      (node (ref "IC4") (pin "24") (pinfunction "PC1(ADC1)_24") (pintype "bidirectional"))
      (node (ref "IC9") (pin "2") (pinfunction "DQ_2") (pintype "bidirectional"))
      (node (ref "R17") (pin "2") (pinfunction "2_2") (pintype "passive"))
    )
    (net (code "77") (name "TX") (class "Default")
      (node (ref "IC4") (pin "31") (pinfunction "PD1(TXD)_31") (pintype "bidirectional"))
      (node (ref "IC5") (pin "11") (pinfunction "T1IN_11") (pintype "input"))
      (node (ref "R8") (pin "1") (pinfunction "1_1") (pintype "passive"))
      (node (ref "TX") (pin "TP") (pinfunction "TP_TP") (pintype "input"))
    )
    (net (code "78") (name "VCC") (class "Default")
      (node (ref "+5V") (pin "TP") (pinfunction "TP_TP") (pintype "input"))
      (node (ref "C11") (pin "-") (pinfunction "-_-") (pintype "passive"))
      (node (ref "C13") (pin "2") (pinfunction "2_2") (pintype "passive"))
      (node (ref "C14") (pin "1") (pinfunction "1_1") (pintype "passive"))
      (node (ref "C15") (pin "1") (pinfunction "1_1") (pintype "passive"))
      (node (ref "C16") (pin "1") (pinfunction "1_1") (pintype "passive"))
      (node (ref "C2") (pin "1") (pinfunction "1_1") (pintype "passive"))
      (node (ref "IC1") (pin "3") (pinfunction "VO_3") (pintype "passive"))
      (node (ref "IC3") (pin "9") (pinfunction "VDD_9") (pintype "power_in"))
      (node (ref "IC4") (pin "18") (pinfunction "AVCC_18") (pintype "bidirectional"))
      (node (ref "IC4") (pin "4") (pinfunction "VCC_4") (pintype "bidirectional"))
      (node (ref "IC4") (pin "6") (pinfunction "VCC_6") (pintype "bidirectional"))
      (node (ref "IC5") (pin "16") (pinfunction "VCC_16") (pintype "bidirectional"))
      (node (ref "IC6") (pin "1") (pinfunction "VCC_1") (pintype "power_in"))
      (node (ref "IC8") (pin "3") (pinfunction "VDD_3") (pintype "power_in"))
      (node (ref "IC9") (pin "3") (pinfunction "VDD_3") (pintype "power_in"))
      (node (ref "R10") (pin "1") (pinfunction "1_1") (pintype "passive"))
      (node (ref "R17") (pin "1") (pinfunction "1_1") (pintype "passive"))
      (node (ref "R18") (pin "1") (pinfunction "1_1") (pintype "passive"))
      (node (ref "R20") (pin "1") (pinfunction "1_1") (pintype "passive"))
      (node (ref "R7") (pin "1") (pinfunction "1_1") (pintype "passive"))
      (node (ref "U$10") (pin "OUT+") (pinfunction "OUT+_OUT+") (pintype "bidirectional"))
      (node (ref "U$5") (pin "+5V") (pinfunction "5V_+5V") (pintype "bidirectional"))
      (node (ref "U$6") (pin "BLA") (pinfunction "BLA_BLA") (pintype "bidirectional"))
      (node (ref "U$6") (pin "VDD") (pinfunction "VDD_VDD") (pintype "bidirectional"))
    )
    (net (code "79") (name "VLOAD_ATT") (class "Default")
      (node (ref "IC4") (pin "26") (pinfunction "PC3(ADC3)_26") (pintype "bidirectional"))
      (node (ref "R12") (pin "1") (pinfunction "1_1") (pintype "passive"))
      (node (ref "R13") (pin "2") (pinfunction "2_2") (pintype "passive"))
      (node (ref "VLOAD_ATT") (pin "TP") (pinfunction "TP_TP") (pintype "input"))
    )
    (net (code "80") (name "VLOAD_DROP") (class "Default")
      (node (ref "IC2") (pin "6") (pinfunction "-IN_6") (pintype "input"))
      (node (ref "IC4") (pin "25") (pinfunction "PC2(ADC2)_25") (pintype "bidirectional"))
      (node (ref "Q1") (pin "3") (pinfunction "S_3") (pintype "passive"))
      (node (ref "Q3") (pin "3") (pinfunction "S_3") (pintype "passive"))
      (node (ref "R4") (pin "1") (pinfunction "1_1") (pintype "passive"))
      (node (ref "R5") (pin "2") (pinfunction "2_2") (pintype "passive"))
      (node (ref "VLOAD_DROP") (pin "TP") (pinfunction "TP_TP") (pintype "input"))
    )
    (net (code "81") (name "unconnected-(H5-MOUNT-PadB3,0)") (class "Default")
      (node (ref "H5") (pin "B3,0") (pinfunction "MOUNT_B3,0") (pintype "passive"))
    )
    (net (code "82") (name "unconnected-(H6-MOUNT-PadB3,0)") (class "Default")
      (node (ref "H6") (pin "B3,0") (pinfunction "MOUNT_B3,0") (pintype "passive"))
    )
    (net (code "83") (name "unconnected-(IC3-GPA5-Pad26)") (class "Default")
      (node (ref "IC3") (pin "26") (pinfunction "GPA5_26") (pintype "bidirectional"))
    )
    (net (code "84") (name "unconnected-(IC3-GPA6-Pad27)") (class "Default")
      (node (ref "IC3") (pin "27") (pinfunction "GPA6_27") (pintype "bidirectional"))
    )
    (net (code "85") (name "unconnected-(IC3-GPA7-Pad28)") (class "Default")
      (node (ref "IC3") (pin "28") (pinfunction "GPA7_28") (pintype "bidirectional"))
    )
    (net (code "86") (name "unconnected-(IC3-INTA-Pad20)") (class "Default")
      (node (ref "IC3") (pin "20") (pinfunction "INTA_20") (pintype "output"))
    )
    (net (code "87") (name "unconnected-(IC3-INTB-Pad19)") (class "Default")
      (node (ref "IC3") (pin "19") (pinfunction "INTB_19") (pintype "output"))
    )
    (net (code "88") (name "unconnected-(IC4-ADC6-Pad19)") (class "Default")
      (node (ref "IC4") (pin "19") (pinfunction "ADC6_19") (pintype "bidirectional"))
    )
    (net (code "89") (name "unconnected-(IC4-ADC7-Pad22)") (class "Default")
      (node (ref "IC4") (pin "22") (pinfunction "ADC7_22") (pintype "bidirectional"))
    )
    (net (code "90") (name "unconnected-(IC5-T2IN-Pad10)") (class "Default")
      (node (ref "IC5") (pin "10") (pinfunction "T2IN_10") (pintype "input"))
    )
    (net (code "91") (name "unconnected-(IC5-T2OUT-Pad7)") (class "Default")
      (node (ref "IC5") (pin "7") (pinfunction "T2OUT_7") (pintype "output"))
    )
    (net (code "92") (name "unconnected-(JP2-Pad1)") (class "Default")
      (node (ref "JP2") (pin "1") (pinfunction "1_1") (pintype "passive"))
    )
    (net (code "93") (name "unconnected-(JP2-Pad7)") (class "Default")
      (node (ref "JP2") (pin "7") (pinfunction "7_7") (pintype "passive"))
    )
    (net (code "94") (name "unconnected-(JP2-Pad8)") (class "Default")
      (node (ref "JP2") (pin "8") (pinfunction "8_8") (pintype "passive"))
    )
    (net (code "95") (name "unconnected-(JP2-Pad9)") (class "Default")
      (node (ref "JP2") (pin "9") (pinfunction "9_9") (pintype "passive"))
    )
    (net (code "96") (name "unconnected-(KK1-K-PadK1)") (class "Default")
      (node (ref "KK1") (pin "K1") (pinfunction "K_K1") (pintype "passive"))
    )
    (net (code "97") (name "unconnected-(KK1-K-PadK2)") (class "Default")
      (node (ref "KK1") (pin "K2") (pinfunction "K_K2") (pintype "passive"))
    )
    (net (code "98") (name "unconnected-(KK3-K-PadK1)") (class "Default")
      (node (ref "KK3") (pin "K1") (pinfunction "K_K1") (pintype "passive"))
    )
    (net (code "99") (name "unconnected-(KK3-K-PadK2)") (class "Default")
      (node (ref "KK3") (pin "K2") (pinfunction "K_K2") (pintype "passive"))
    )
  )
)
